# nycrsign.net
KiCad netlist of a schematic drawn in EAGLE
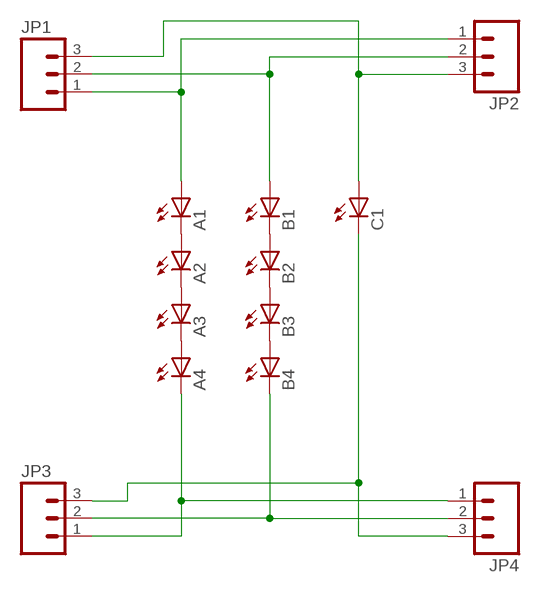
[diagram p0: schematic, sheet 1]

(export (version "E")
  (design (tool "Eeschema 10.0.6"))
  (components
    (comp (ref "A1")
      (value "LED5MM")
      (footprint "eagle-import:LED5MM")
      (libsource (lib "eagle-import") (part "LED5MM"))
    )
    (comp (ref "A2")
      (value "LED5MM")
      (footprint "eagle-import:LED5MM")
      (libsource (lib "eagle-import") (part "LED5MM"))
    )
    (comp (ref "A3")
      (value "LED5MM")
      (footprint "eagle-import:LED5MM")
      (libsource (lib "eagle-import") (part "LED5MM"))
    )
    (comp (ref "A4")
      (value "LED5MM")
      (footprint "eagle-import:LED5MM")
      (libsource (lib "eagle-import") (part "LED5MM"))
    )
    (comp (ref "B1")
      (value "LED5MM")
      (footprint "eagle-import:LED5MM")
      (libsource (lib "eagle-import") (part "LED5MM"))
    )
    (comp (ref "B2")
      (value "LED5MM")
      (footprint "eagle-import:LED5MM")
      (libsource (lib "eagle-import") (part "LED5MM"))
    )
    (comp (ref "B3")
      (value "LED5MM")
      (footprint "eagle-import:LED5MM")
      (libsource (lib "eagle-import") (part "LED5MM"))
    )
    (comp (ref "B4")
      (value "LED5MM")
      (footprint "eagle-import:LED5MM")
      (libsource (lib "eagle-import") (part "LED5MM"))
    )
    (comp (ref "C1")
      (value "LED5MM")
      (footprint "eagle-import:LED5MM")
      (libsource (lib "eagle-import") (part "LED5MM"))
    )
    (comp (ref "JP1")
      (value "M03LONGPADS")
      (footprint "eagle-import:1X03_LONGPADS")
      (libsource (lib "eagle-import") (part "M03LONGPADS"))
    )
    (comp (ref "JP2")
      (value "M03LONGPADS")
      (footprint "eagle-import:1X03_LONGPADS")
      (libsource (lib "eagle-import") (part "M03LONGPADS"))
    )
    (comp (ref "JP3")
      (value "M03LONGPADS")
      (footprint "eagle-import:1X03_LONGPADS")
      (libsource (lib "eagle-import") (part "M03LONGPADS"))
    )
    (comp (ref "JP4")
      (value "M03LONGPADS")
      (footprint "eagle-import:1X03_LONGPADS")
      (libsource (lib "eagle-import") (part "M03LONGPADS"))
    )
  )
  (nets
    (net (code "1") (name "Net-(A1-C)") (class "Default")
      (node (ref "A1") (pin "K") (pinfunction "C_K") (pintype "passive"))
      (node (ref "A2") (pin "A") (pinfunction "A_A") (pintype "passive"))
    )
    (net (code "2") (name "Net-(A1-PadA)") (class "Default")
      (node (ref "A1") (pin "A") (pinfunction "A_A") (pintype "passive"))
      (node (ref "JP1") (pin "1") (pinfunction "1_1") (pintype "passive"))
      (node (ref "JP2") (pin "1") (pinfunction "1_1") (pintype "passive"))
    )
    (net (code "3") (name "Net-(A2-C)") (class "Default")
      (node (ref "A2") (pin "K") (pinfunction "C_K") (pintype "passive"))
      (node (ref "A3") (pin "A") (pinfunction "A_A") (pintype "passive"))
    )
    (net (code "4") (name "Net-(A3-C)") (class "Default")
      (node (ref "A3") (pin "K") (pinfunction "C_K") (pintype "passive"))
      (node (ref "A4") (pin "A") (pinfunction "A_A") (pintype "passive"))
    )
    (net (code "5") (name "Net-(A4-C)") (class "Default")
      (node (ref "A4") (pin "K") (pinfunction "C_K") (pintype "passive"))
      (node (ref "JP3") (pin "1") (pinfunction "1_1") (pintype "passive"))
      (node (ref "JP4") (pin "1") (pinfunction "1_1") (pintype "passive"))
    )
    (net (code "6") (name "Net-(B1-C)") (class "Default")
      (node (ref "B1") (pin "K") (pinfunction "C_K") (pintype "passive"))
      (node (ref "B2") (pin "A") (pinfunction "A_A") (pintype "passive"))
    )
    (net (code "7") (name "Net-(B1-PadA)") (class "Default")
      (node (ref "B1") (pin "A") (pinfunction "A_A") (pintype "passive"))
      (node (ref "JP1") (pin "2") (pinfunction "2_2") (pintype "passive"))
      (node (ref "JP2") (pin "2") (pinfunction "2_2") (pintype "passive"))
    )
    (net (code "8") (name "Net-(B2-C)") (class "Default")
      (node (ref "B2") (pin "K") (pinfunction "C_K") (pintype "passive"))
      (node (ref "B3") (pin "A") (pinfunction "A_A") (pintype "passive"))
    )
    (net (code "9") (name "Net-(B3-C)") (class "Default")
      (node (ref "B3") (pin "K") (pinfunction "C_K") (pintype "passive"))
      (node (ref "B4") (pin "A") (pinfunction "A_A") (pintype "passive"))
    )
    (net (code "10") (name "Net-(B4-C)") (class "Default")
      (node (ref "B4") (pin "K") (pinfunction "C_K") (pintype "passive"))
      (node (ref "JP3") (pin "2") (pinfunction "2_2") (pintype "passive"))
      (node (ref "JP4") (pin "2") (pinfunction "2_2") (pintype "passive"))
    )
    (net (code "11") (name "Net-(C1-C)") (class "Default")
      (node (ref "C1") (pin "K") (pinfunction "C_K") (pintype "passive"))
      (node (ref "JP3") (pin "3") (pinfunction "3_3") (pintype "passive"))
      (node (ref "JP4") (pin "3") (pinfunction "3_3") (pintype "passive"))
    )
    (net (code "12") (name "Net-(C1-PadA)") (class "Default")
      (node (ref "C1") (pin "A") (pinfunction "A_A") (pintype "passive"))
      (node (ref "JP1") (pin "3") (pinfunction "3_3") (pintype "passive"))
      (node (ref "JP2") (pin "3") (pinfunction "3_3") (pintype "passive"))
    )
  )
)
